# sd_reader.net
KiCad netlist of a schematic drawn in EasyEDA Pro
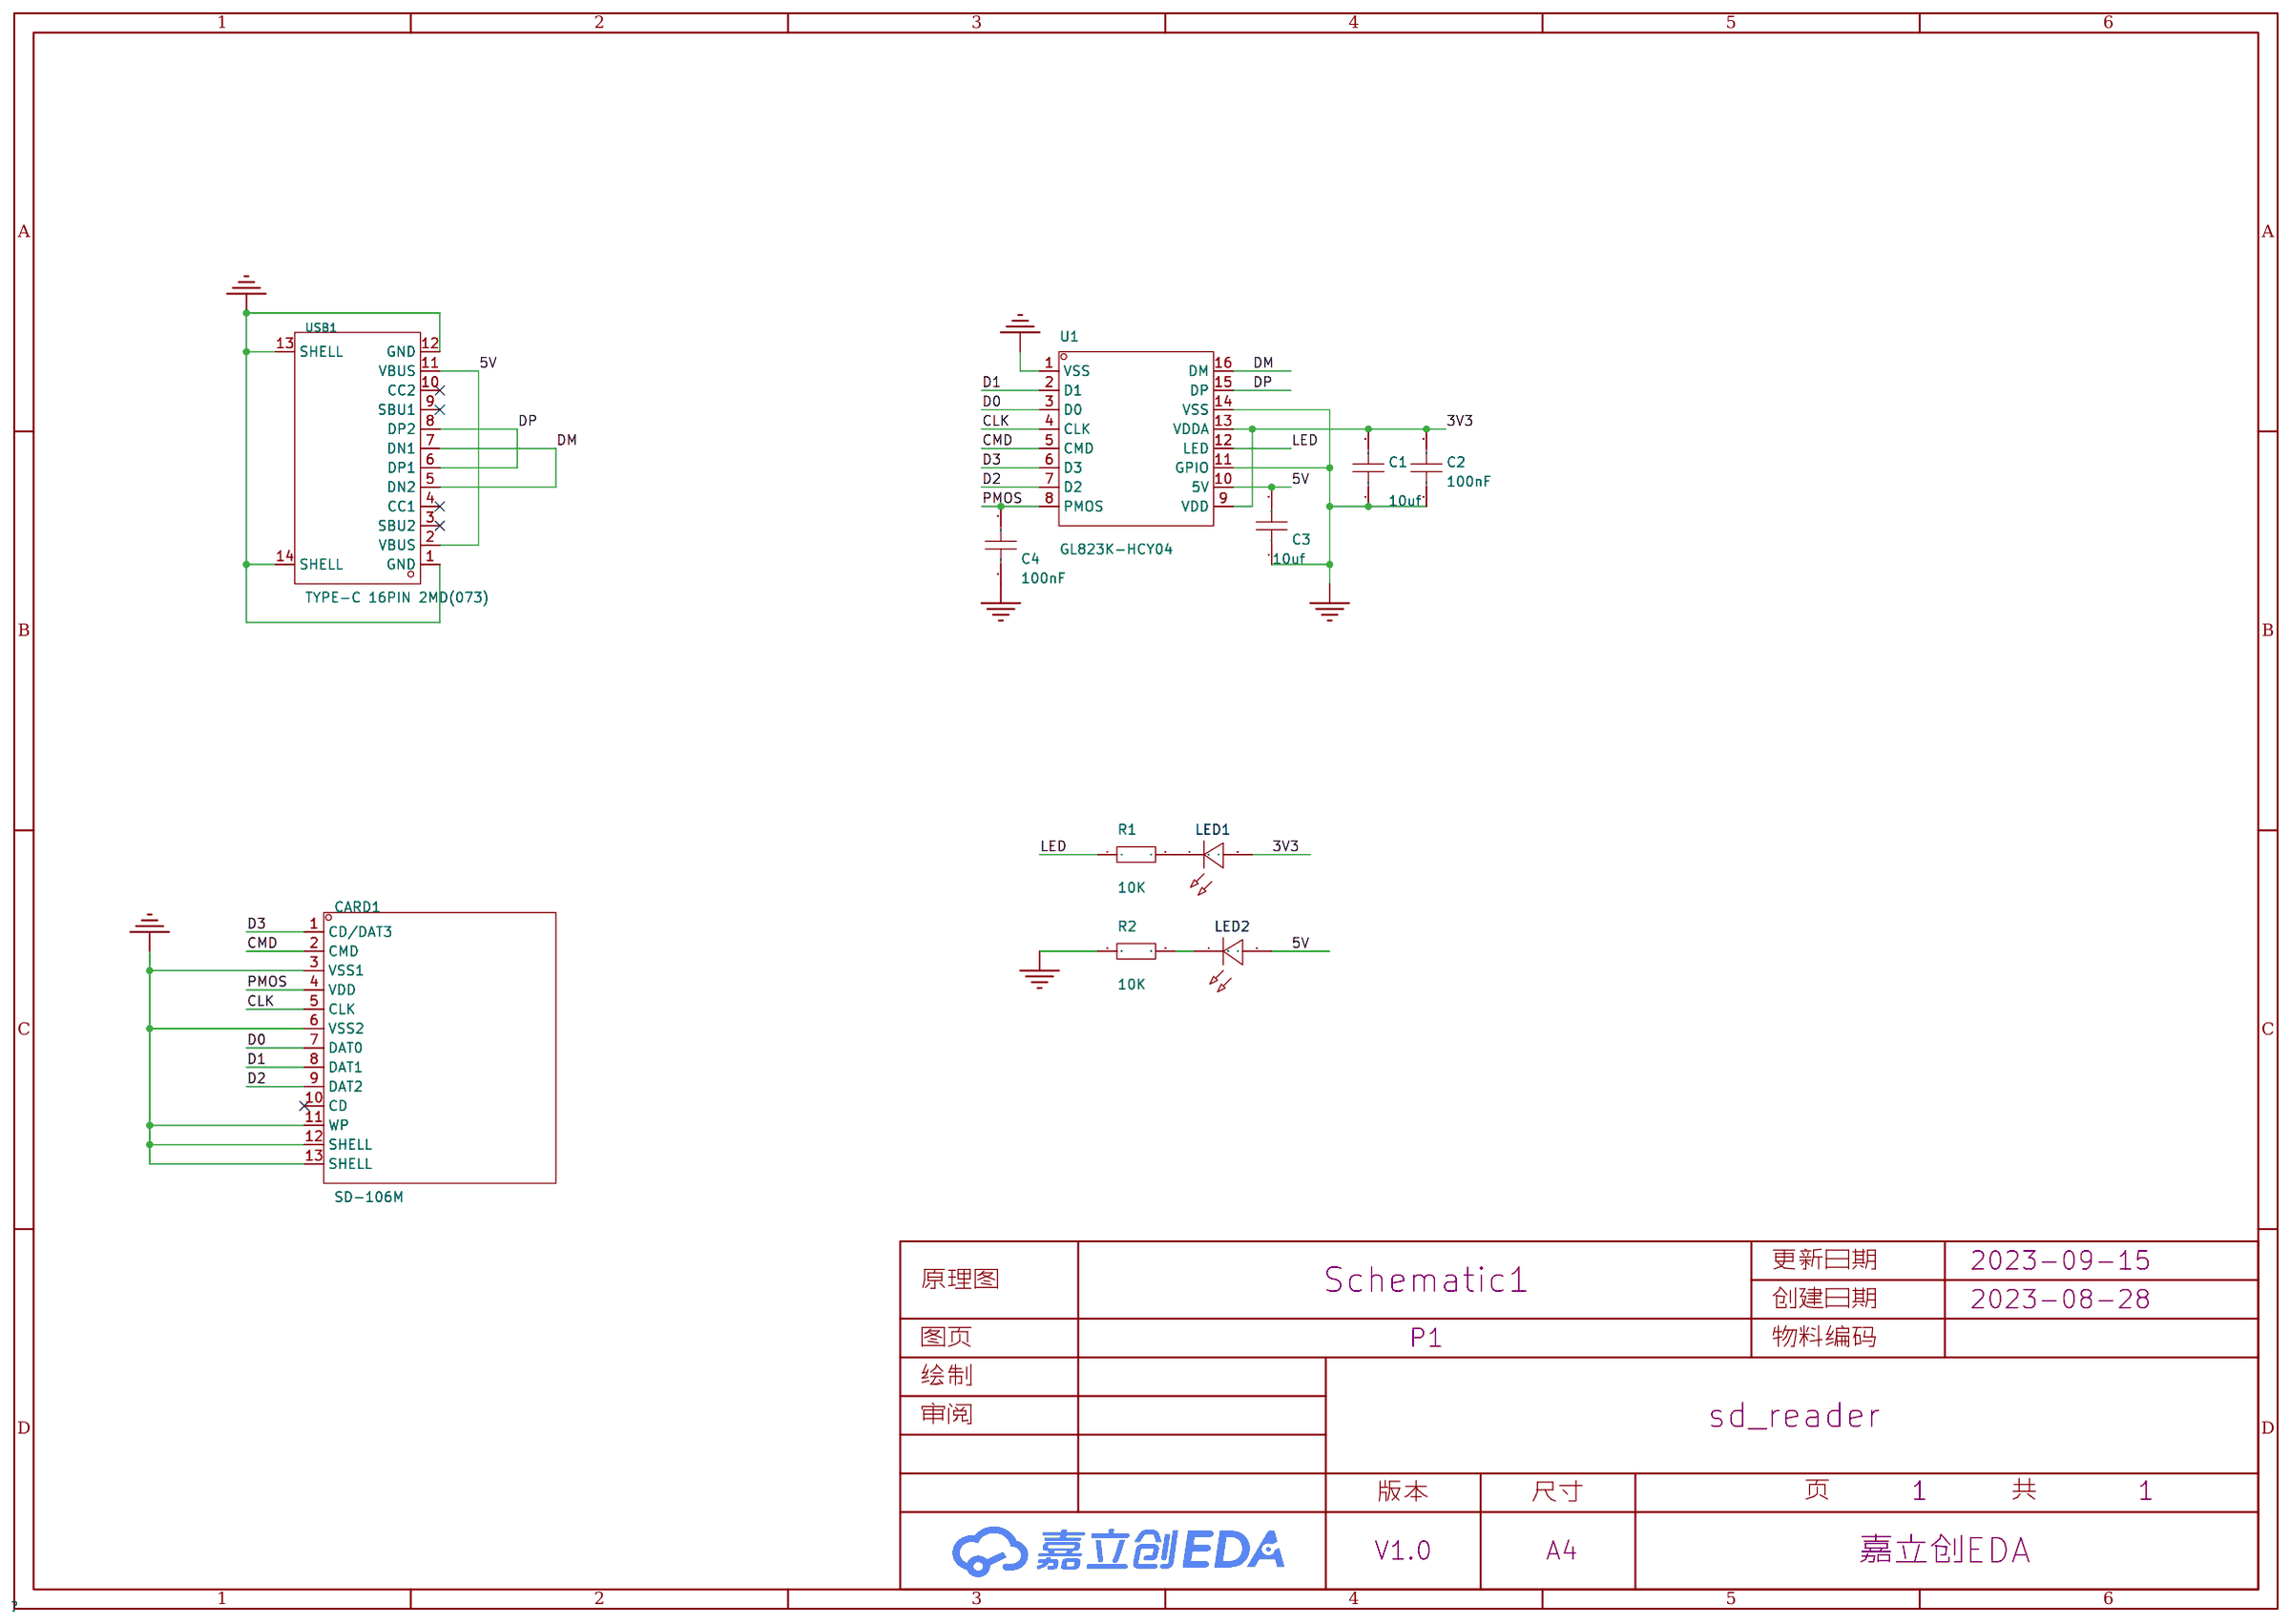
[diagram p0: schematic sheet]

(export (version "E")
  (design (tool "Eeschema 10.0.6"))
  (components
    (comp (ref "C1")
      (value "10uf")
      (footprint "easyedapro:C0603")
      (libsource (lib "easyedapro") (part "CapAcitance"))
    )
    (comp (ref "C2")
      (value "100nF")
      (footprint "easyedapro:C0603")
      (libsource (lib "easyedapro") (part "CapAcitance"))
    )
    (comp (ref "C3")
      (value "10uf")
      (footprint "easyedapro:C0603")
      (libsource (lib "easyedapro") (part "CapAcitance"))
    )
    (comp (ref "C4")
      (value "100nF")
      (footprint "easyedapro:C0603")
      (libsource (lib "easyedapro") (part "CapAcitance"))
    )
    (comp (ref "CARD1")
      (value "SD-106M")
      (footprint "easyedapro:SD-SMD_SD-106M")
      (description "卡连接方式:自弹式;卡类型:标准SD卡;连接器类型:卡座;本体最大高度:2.9mm;触头材质:C5191;触头镀层:金;工作温度范围:-45°C~+85°C;焊接温度(最大值):260°C;")
      (fields (field (name "Manufacturer") "XUNPU(讯普)"))
      (libsource (lib "easyedapro") (part "SD-106M"))
    )
    (comp (ref "LED1")
      (value "~")
      (footprint "easyedapro:LED_0603")
      (libsource (lib "easyedapro") (part "LED_B"))
    )
    (comp (ref "LED2")
      (value "~")
      (footprint "easyedapro:LED_0603")
      (libsource (lib "easyedapro") (part "LED_G"))
    )
    (comp (ref "R1") (value "10K") (footprint "easyedapro:R0603") (libsource (lib "easyedapro") (part "电阻")))
    (comp (ref "R2") (value "10K") (footprint "easyedapro:R0603") (libsource (lib "easyedapro") (part "电阻")))
    (comp (ref "U1")
      (value "GL823K-HCY04")
      (footprint "easyedapro:SSOP-16_L4.9-W3.9-P0.64-LS6.0-BL")
      (description "类型:-;协议类别:-;驱动器/接收器数:-;数据速率:-;")
      (fields (field (name "Manufacturer") "GENESYS(创惟)"))
      (libsource (lib "easyedapro") (part "GL823K-HCY04"))
    )
    (comp (ref "USB1")
      (value "TYPE-C 16PIN 2MD(073)")
      (footprint "easyedapro:USB-C-SMD_TYPE-C-6PIN-2MD-073")
      (description "连接器类型:Type-C;标准:-;公母:母座;触点数量:16;端口数量:1;安装方式:卧贴;额定电流 - 电源:5A;工作温度范围:-25°C~+85°C;")
      (fields (field (name "Manufacturer") "SHOU HAN(首韩)"))
      (libsource (lib "easyedapro") (part "TYPE-C 16PIN 2MD(073)"))
    )
  )
  (nets
    (net (code "1") (name "/3V3") (class "Default")
      (node (ref "C1") (pin "2") (pinfunction "2_2") (pintype "input"))
      (node (ref "C2") (pin "2") (pinfunction "2_2") (pintype "input"))
      (node (ref "LED1") (pin "2") (pinfunction "A_2") (pintype "input"))
      (node (ref "U1") (pin "13") (pinfunction "VDDA_13") (pintype "input"))
      (node (ref "U1") (pin "9") (pinfunction "VDD_9") (pintype "input"))
    )
    (net (code "2") (name "/5V") (class "Default")
      (node (ref "C3") (pin "2") (pinfunction "2_2") (pintype "input"))
      (node (ref "LED2") (pin "2") (pinfunction "A_2") (pintype "input"))
      (node (ref "U1") (pin "10") (pinfunction "5V_10") (pintype "input"))
      (node (ref "USB1") (pin "11") (pinfunction "VBUS_11") (pintype "input"))
      (node (ref "USB1") (pin "2") (pinfunction "VBUS_2") (pintype "input"))
    )
    (net (code "3") (name "/CLK") (class "Default")
      (node (ref "CARD1") (pin "5") (pinfunction "CLK_5") (pintype "input"))
      (node (ref "U1") (pin "4") (pinfunction "CLK_4") (pintype "input"))
    )
    (net (code "4") (name "/CMD") (class "Default")
      (node (ref "CARD1") (pin "2") (pinfunction "CMD_2") (pintype "input"))
      (node (ref "U1") (pin "5") (pinfunction "CMD_5") (pintype "input"))
    )
    (net (code "5") (name "/D0") (class "Default")
      (node (ref "CARD1") (pin "7") (pinfunction "DAT0_7") (pintype "input"))
      (node (ref "U1") (pin "3") (pinfunction "D0_3") (pintype "input"))
    )
    (net (code "6") (name "/D1") (class "Default")
      (node (ref "CARD1") (pin "8") (pinfunction "DAT1_8") (pintype "input"))
      (node (ref "U1") (pin "2") (pinfunction "D1_2") (pintype "input"))
    )
    (net (code "7") (name "/D2") (class "Default")
      (node (ref "CARD1") (pin "9") (pinfunction "DAT2_9") (pintype "input"))
      (node (ref "U1") (pin "7") (pinfunction "D2_7") (pintype "input"))
    )
    (net (code "8") (name "/D3") (class "Default")
      (node (ref "CARD1") (pin "1") (pinfunction "CD/DAT3_1") (pintype "input"))
      (node (ref "U1") (pin "6") (pinfunction "D3_6") (pintype "input"))
    )
    (net (code "9") (name "/DM") (class "Default")
      (node (ref "U1") (pin "16") (pinfunction "DM_16") (pintype "input"))
      (node (ref "USB1") (pin "5") (pinfunction "DN2_5") (pintype "input"))
      (node (ref "USB1") (pin "7") (pinfunction "DN1_7") (pintype "input"))
    )
    (net (code "10") (name "/DP") (class "Default")
      (node (ref "U1") (pin "15") (pinfunction "DP_15") (pintype "input"))
      (node (ref "USB1") (pin "6") (pinfunction "DP1_6") (pintype "input"))
      (node (ref "USB1") (pin "8") (pinfunction "DP2_8") (pintype "input"))
    )
    (net (code "11") (name "/LED") (class "Default")
      (node (ref "R1") (pin "1") (pinfunction "1_1") (pintype "input"))
      (node (ref "U1") (pin "12") (pinfunction "LED_12") (pintype "input"))
    )
    (net (code "12") (name "/PMOS") (class "Default")
      (node (ref "C4") (pin "2") (pinfunction "2_2") (pintype "input"))
      (node (ref "CARD1") (pin "4") (pinfunction "VDD_4") (pintype "input"))
      (node (ref "U1") (pin "8") (pinfunction "PMOS_8") (pintype "input"))
    )
    (net (code "13") (name "GND") (class "Default")
      (node (ref "C1") (pin "1") (pinfunction "1_1") (pintype "input"))
      (node (ref "C2") (pin "1") (pinfunction "1_1") (pintype "input"))
      (node (ref "C3") (pin "1") (pinfunction "1_1") (pintype "input"))
      (node (ref "C4") (pin "1") (pinfunction "1_1") (pintype "input"))
      (node (ref "CARD1") (pin "11") (pinfunction "WP_11") (pintype "input"))
      (node (ref "CARD1") (pin "12") (pinfunction "SHELL_12") (pintype "input"))
      (node (ref "CARD1") (pin "13") (pinfunction "SHELL_13") (pintype "input"))
      (node (ref "CARD1") (pin "3") (pinfunction "VSS1_3") (pintype "input"))
      (node (ref "CARD1") (pin "6") (pinfunction "VSS2_6") (pintype "input"))
      (node (ref "R2") (pin "1") (pinfunction "1_1") (pintype "input"))
      (node (ref "U1") (pin "1") (pinfunction "VSS_1") (pintype "input"))
      (node (ref "U1") (pin "11") (pinfunction "GPIO_11") (pintype "input"))
      (node (ref "U1") (pin "14") (pinfunction "VSS_14") (pintype "input"))
      (node (ref "USB1") (pin "1") (pinfunction "GND_1") (pintype "input"))
      (node (ref "USB1") (pin "12") (pinfunction "GND_12") (pintype "input"))
      (node (ref "USB1") (pin "13") (pinfunction "SHELL_13") (pintype "input"))
      (node (ref "USB1") (pin "14") (pinfunction "SHELL_14") (pintype "input"))
    )
    (net (code "14") (name "Net-(LED1-C)") (class "Default")
      (node (ref "LED1") (pin "1") (pinfunction "C_1") (pintype "input"))
      (node (ref "R1") (pin "2") (pinfunction "2_2") (pintype "input"))
    )
    (net (code "15") (name "Net-(LED2-C)") (class "Default")
      (node (ref "LED2") (pin "1") (pinfunction "C_1") (pintype "input"))
      (node (ref "R2") (pin "2") (pinfunction "2_2") (pintype "input"))
    )
    (net (code "16") (name "unconnected-(CARD1-CD-Pad10)") (class "Default")
      (node (ref "CARD1") (pin "10") (pinfunction "CD_10") (pintype "input+no_connect"))
    )
    (net (code "17") (name "unconnected-(USB1-CC1-Pad4)") (class "Default")
      (node (ref "USB1") (pin "4") (pinfunction "CC1_4") (pintype "input+no_connect"))
    )
    (net (code "18") (name "unconnected-(USB1-CC2-Pad10)") (class "Default")
      (node (ref "USB1") (pin "10") (pinfunction "CC2_10") (pintype "input+no_connect"))
    )
    (net (code "19") (name "unconnected-(USB1-SBU1-Pad9)") (class "Default")
      (node (ref "USB1") (pin "9") (pinfunction "SBU1_9") (pintype "input+no_connect"))
    )
    (net (code "20") (name "unconnected-(USB1-SBU2-Pad3)") (class "Default")
      (node (ref "USB1") (pin "3") (pinfunction "SBU2_3") (pintype "input+no_connect"))
    )
  )
)
